# node_motor.net
KiCad netlist of a schematic drawn in EAGLE
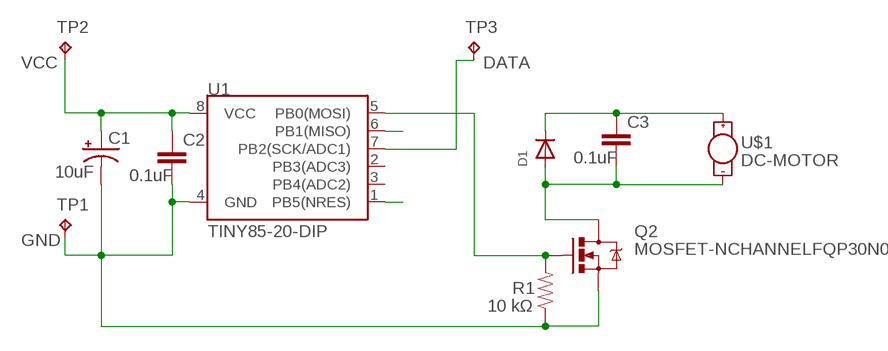
[diagram p0: schematic, sheet 1]

(export (version "E")
  (design (tool "Eeschema 10.0.6"))
  (components
    (comp (ref "C1")
      (value "10uF")
      (footprint "eagle-import:EIA3216")
      (libsource (lib "eagle-import") (part "10UF-16V-10%(TANT)"))
    )
    (comp (ref "C2")
      (value "0.1uF")
      (footprint "eagle-import:1206")
      (libsource (lib "eagle-import") (part "CAP1206"))
    )
    (comp (ref "C3")
      (value "0.1uF")
      (footprint "eagle-import:1206")
      (libsource (lib "eagle-import") (part "CAP1206"))
    )
    (comp (ref "D1")
      (value "DIODESMA")
      (footprint "eagle-import:SMADIODE")
      (libsource (lib "eagle-import") (part "DIODESMA"))
    )
    (comp (ref "Q2")
      (value "MOSFET-NCHANNELFQP30N06L")
      (footprint "eagle-import:TO220V")
      (libsource (lib "eagle-import") (part "MOSFET-NCHANNELFQP30N06L"))
    )
    (comp (ref "R1")
      (value "10 kΩ")
      (footprint "eagle-import:1206")
      (libsource (lib "eagle-import") (part "RESISTOR1206"))
    )
    (comp (ref "TP1")
      (value "PADSTP13R")
      (footprint "eagle-import:CIRCLE-PAD-1_4")
      (fields (field (name "TP_SIGNAL_NAME") "GND"))
      (libsource (lib "eagle-import") (part "PADSTP13R"))
    )
    (comp (ref "TP2")
      (value "PADSTP13R")
      (footprint "eagle-import:CIRCLE-PAD-1_4")
      (fields (field (name "TP_SIGNAL_NAME") "VCC"))
      (libsource (lib "eagle-import") (part "PADSTP13R"))
    )
    (comp (ref "TP3")
      (value "PADSTP13R")
      (footprint "eagle-import:CIRCLE-PAD-1_4")
      (fields (field (name "TP_SIGNAL_NAME") "DATA"))
      (libsource (lib "eagle-import") (part "PADSTP13R"))
    )
    (comp (ref "U$1")
      (value "DC-MOTOR")
      (footprint "eagle-import:DC-MOTOR-20MM")
      (libsource (lib "eagle-import") (part "DC-MOTOR"))
    )
    (comp (ref "U1")
      (value "TINY85-20-DIP")
      (footprint "eagle-import:DIP08")
      (libsource (lib "eagle-import") (part "ATTINY45TINY45-20-DIP"))
    )
  )
  (nets
    (net (code "1") (name "Net-(C1-+)") (class "Default")
      (node (ref "C1") (pin "A") (pinfunction "+_A") (pintype "passive"))
      (node (ref "C2") (pin "1") (pinfunction "1_1") (pintype "passive"))
      (node (ref "TP2") (pin "TP") (pinfunction "TP_TP") (pintype "input"))
      (node (ref "U1") (pin "8") (pinfunction "VCC_8") (pintype "bidirectional"))
    )
    (net (code "2") (name "Net-(C1--)") (class "Default")
      (node (ref "C1") (pin "C") (pinfunction "-_C") (pintype "passive"))
      (node (ref "C2") (pin "2") (pinfunction "2_2") (pintype "passive"))
      (node (ref "Q2") (pin "3") (pinfunction "S_3") (pintype "passive"))
      (node (ref "R1") (pin "1") (pinfunction "1_1") (pintype "passive"))
      (node (ref "TP1") (pin "TP") (pinfunction "TP_TP") (pintype "input"))
      (node (ref "U1") (pin "4") (pinfunction "GND_4") (pintype "bidirectional"))
    )
    (net (code "3") (name "Net-(C3-Pad1)") (class "Default")
      (node (ref "C3") (pin "1") (pinfunction "1_1") (pintype "passive"))
      (node (ref "D1") (pin "C") (pinfunction "C_C") (pintype "passive"))
      (node (ref "U$1") (pin "+") (pinfunction "+_+") (pintype "bidirectional"))
    )
    (net (code "4") (name "Net-(Q2-D)") (class "Default")
      (node (ref "C3") (pin "2") (pinfunction "2_2") (pintype "passive"))
      (node (ref "D1") (pin "A") (pinfunction "A_A") (pintype "passive"))
      (node (ref "Q2") (pin "2") (pinfunction "D_2") (pintype "passive"))
      (node (ref "U$1") (pin "-") (pinfunction "-_-") (pintype "bidirectional"))
    )
    (net (code "5") (name "Net-(Q2-G)") (class "Default")
      (node (ref "Q2") (pin "1") (pinfunction "G_1") (pintype "passive"))
      (node (ref "R1") (pin "2") (pinfunction "2_2") (pintype "passive"))
      (node (ref "U1") (pin "5") (pinfunction "PB0(MOSI)_5") (pintype "bidirectional"))
    )
    (net (code "6") (name "Net-(U1-PB2(SCK{slash}ADC1))") (class "Default")
      (node (ref "TP3") (pin "TP") (pinfunction "TP_TP") (pintype "input"))
      (node (ref "U1") (pin "7") (pinfunction "PB2(SCK/ADC1)_7") (pintype "bidirectional"))
    )
    (net (code "7") (name "unconnected-(U1-PB1(MISO)-Pad6)") (class "Default")
      (node (ref "U1") (pin "6") (pinfunction "PB1(MISO)_6") (pintype "bidirectional"))
    )
    (net (code "8") (name "unconnected-(U1-PB3(ADC3)-Pad2)") (class "Default")
      (node (ref "U1") (pin "2") (pinfunction "PB3(ADC3)_2") (pintype "bidirectional"))
    )
    (net (code "9") (name "unconnected-(U1-PB4(ADC2)-Pad3)") (class "Default")
      (node (ref "U1") (pin "3") (pinfunction "PB4(ADC2)_3") (pintype "bidirectional"))
    )
    (net (code "10") (name "unconnected-(U1-PB5(NRES)-Pad1)") (class "Default")
      (node (ref "U1") (pin "1") (pinfunction "PB5(NRES)_1") (pintype "bidirectional"))
    )
  )
)
